# SCH_LFR_BODY_PCB_1_2025-05-22.net
KiCad netlist of a schematic drawn in EasyEDA
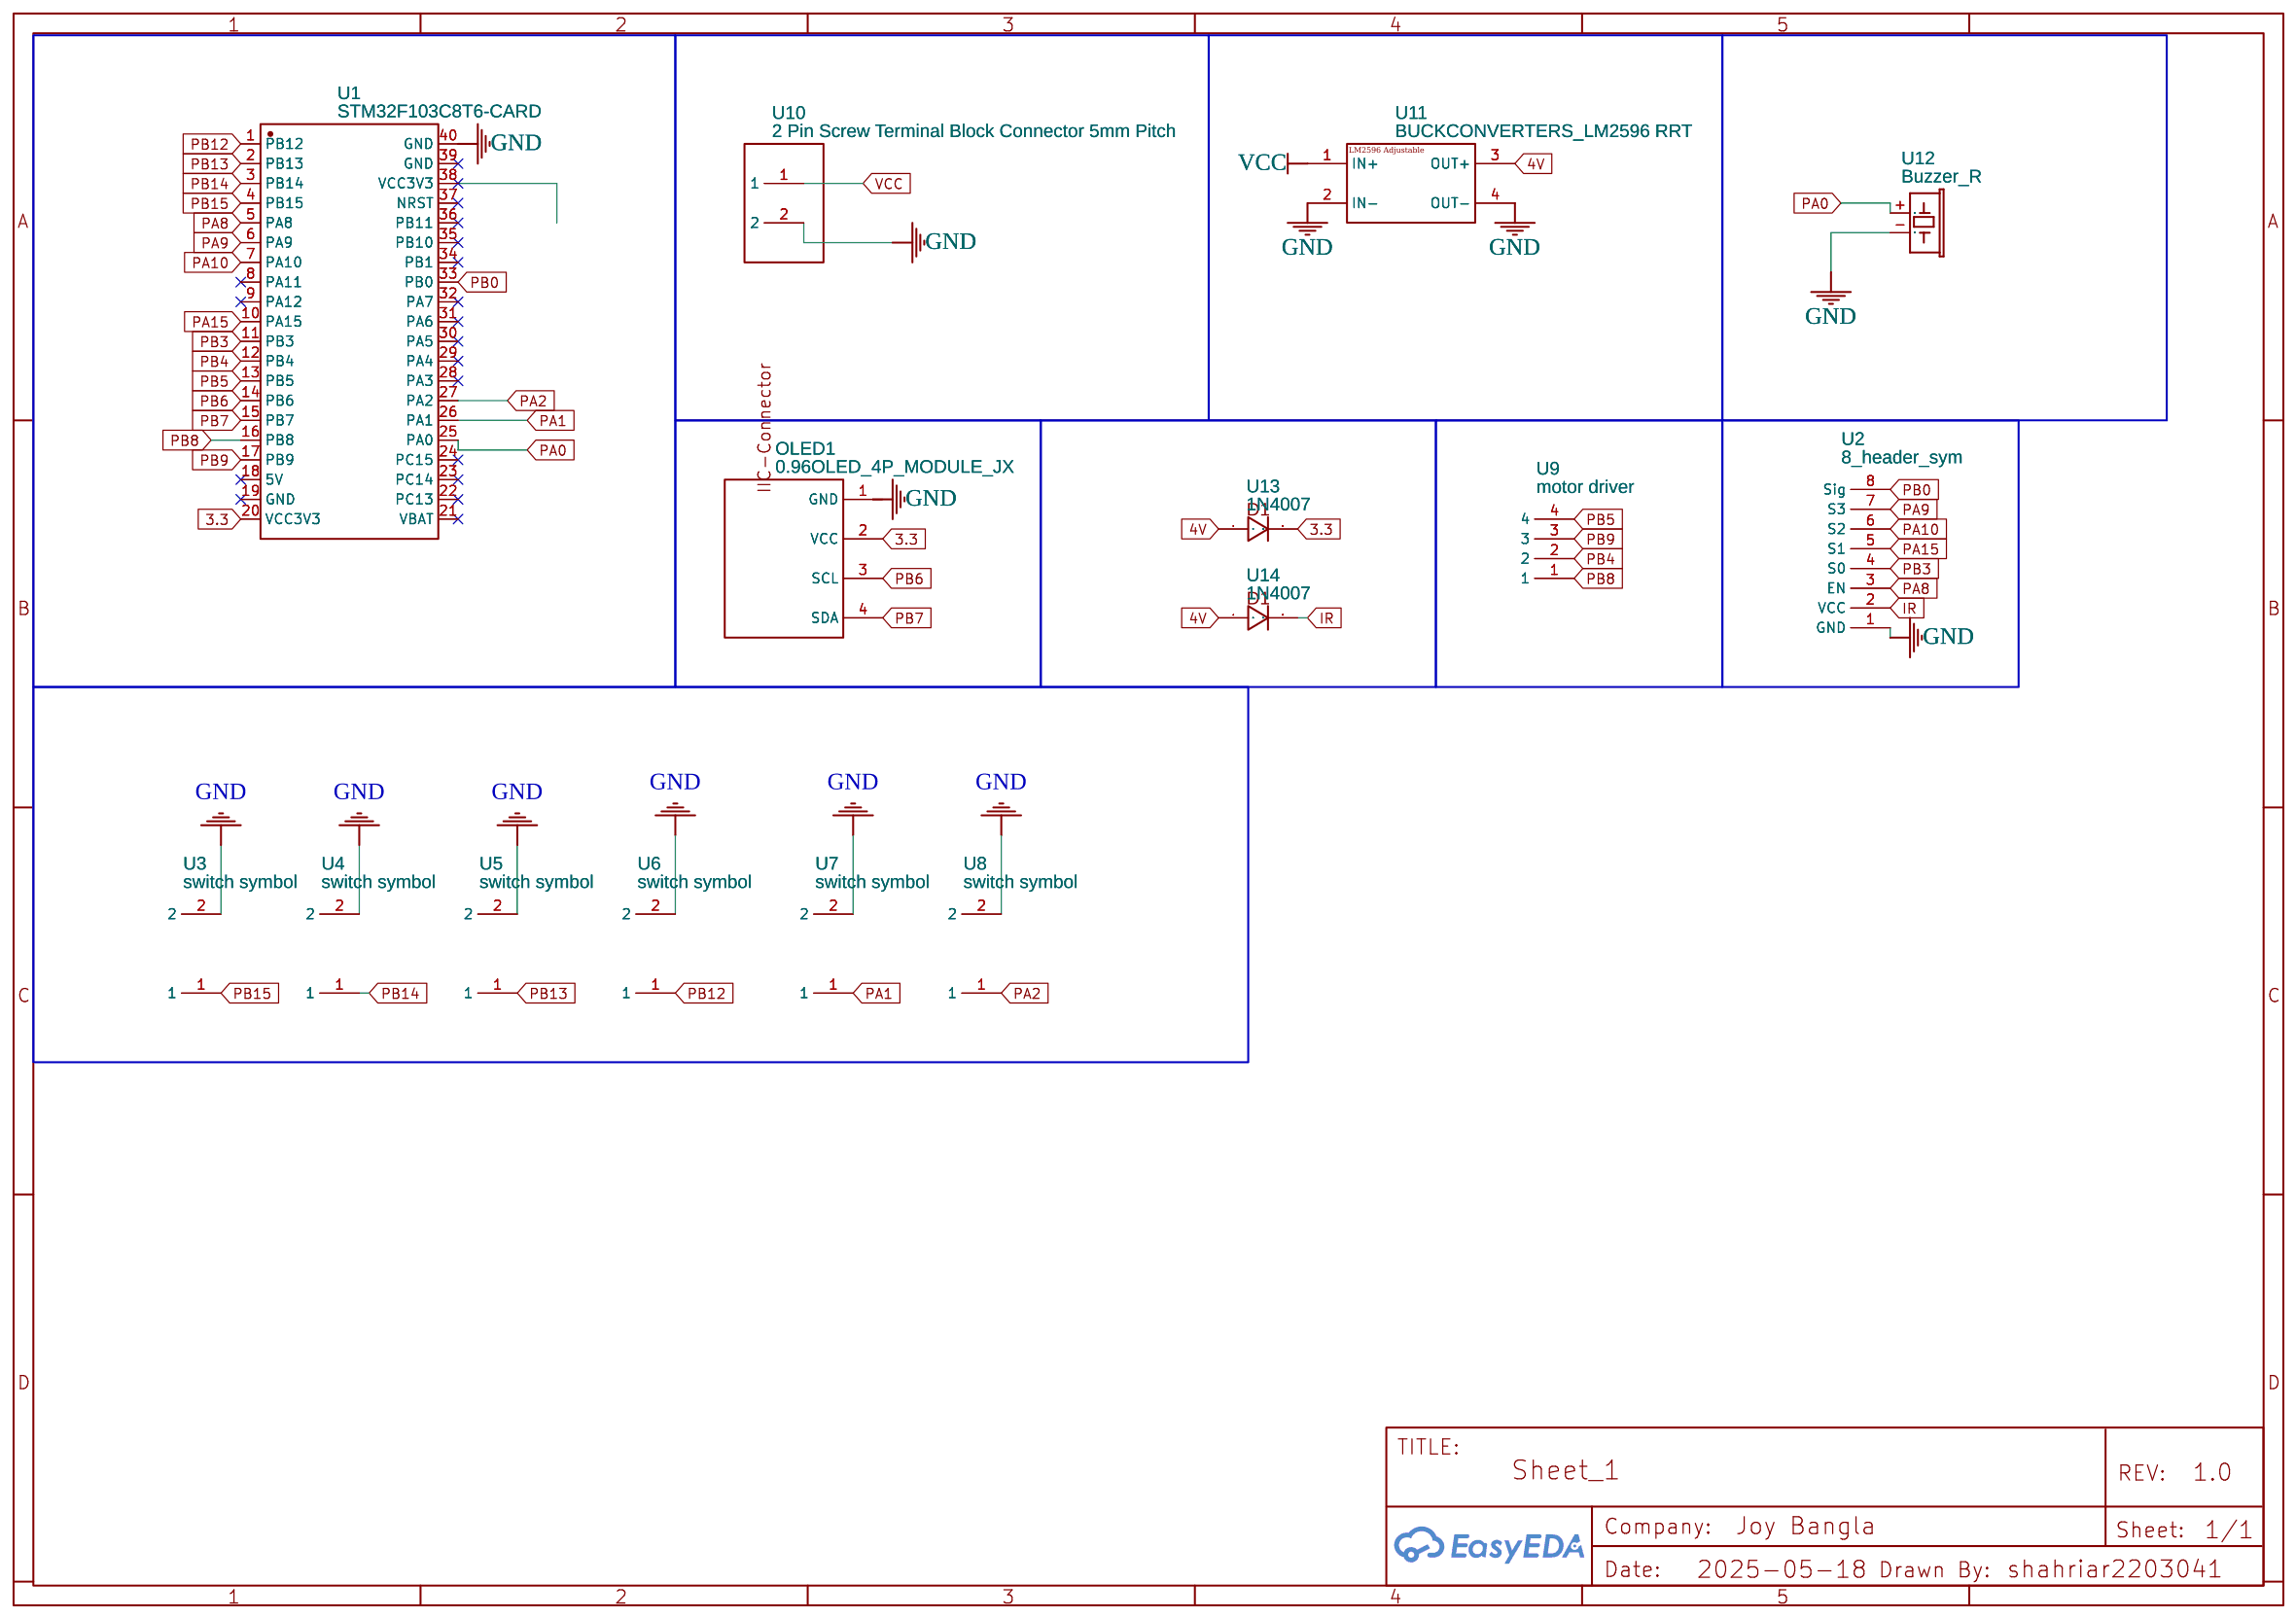
[diagram p0: schematic sheet]

(export (version "E")
  (design (tool "Eeschema 10.0.6"))
  (components
    (comp (ref "OLED1") (value "0.96OLED_4P_MODULE_JX") (libsource (lib "") (part "0.96OLED_4P_MODULE_JX")))
    (comp (ref "U1")
      (value "STM32F103C8T6-CARD")
      (fields (field (name "Manufacturer Part") "STM32F103C8T6-Card"))
      (libsource (lib "") (part "STM32F103C8T6-CARD"))
    )
    (comp (ref "U2") (value "8_header_sym") (libsource (lib "") (part "8_header_sym")))
    (comp (ref "U3") (value "switch symbol") (libsource (lib "") (part "switch symbol")))
    (comp (ref "U4") (value "switch symbol") (libsource (lib "") (part "switch symbol")))
    (comp (ref "U5") (value "switch symbol") (libsource (lib "") (part "switch symbol")))
    (comp (ref "U6") (value "switch symbol") (libsource (lib "") (part "switch symbol")))
    (comp (ref "U7") (value "switch symbol") (libsource (lib "") (part "switch symbol")))
    (comp (ref "U8") (value "switch symbol") (libsource (lib "") (part "switch symbol")))
    (comp (ref "U9") (value "motor driver") (libsource (lib "") (part "motor driver")))
    (comp (ref "U10")
      (value "2 Pin Screw Terminal Block Connector 5mm Pitch")
      (fields (field (name "Manufacturer Part") "EK8365C") (field (name "Manufacturer") "Gikfun"))
      (libsource (lib "") (part "Gikfun 2 Pin Screw Terminal Block Connector 5mm Pitch EK8365C Schematic"))
    )
    (comp (ref "U11")
      (value "BUCKCONVERTERS_LM2596 RRT")
      (libsource (lib "") (part "BuckConverters_LM2596_Adj"))
    )
    (comp (ref "U12") (value "Buzzer_R") (libsource (lib "") (part "Buzzer_R")))
    (comp (ref "U13") (value "1N4007") (libsource (lib "") (part "1N4007")))
    (comp (ref "U14") (value "1N4007") (libsource (lib "") (part "1N4007")))
  )
  (nets
    (net (code "1") (name "3.3") (class "Default")
      (node (ref "OLED1") (pin "2") (pinfunction "VCC_2") (pintype "unspecified"))
      (node (ref "U1") (pin "20") (pinfunction "VCC3V3_20") (pintype "unspecified"))
      (node (ref "U13") (pin "2") (pinfunction "1_2") (pintype "unspecified"))
    )
    (net (code "2") (name "4V") (class "Default")
      (node (ref "U11") (pin "3") (pinfunction "OUT+_3") (pintype "unspecified"))
      (node (ref "U13") (pin "1") (pinfunction "2_1") (pintype "unspecified"))
      (node (ref "U14") (pin "1") (pinfunction "2_1") (pintype "unspecified"))
    )
    (net (code "3") (name "GND") (class "Default")
      (node (ref "OLED1") (pin "1") (pinfunction "GND_1") (pintype "unspecified"))
      (node (ref "U1") (pin "40") (pinfunction "GND_40") (pintype "unspecified"))
      (node (ref "U10") (pin "2") (pinfunction "2_2") (pintype "unspecified"))
      (node (ref "U11") (pin "2") (pinfunction "IN-_2") (pintype "unspecified"))
      (node (ref "U11") (pin "4") (pinfunction "OUT-_4") (pintype "unspecified"))
      (node (ref "U12") (pin "-") (pinfunction "2_-") (pintype "unspecified"))
      (node (ref "U2") (pin "1") (pinfunction "GND_1") (pintype "unspecified"))
      (node (ref "U3") (pin "2") (pinfunction "2_2") (pintype "unspecified"))
      (node (ref "U4") (pin "2") (pinfunction "2_2") (pintype "unspecified"))
      (node (ref "U5") (pin "2") (pinfunction "2_2") (pintype "unspecified"))
      (node (ref "U6") (pin "2") (pinfunction "2_2") (pintype "unspecified"))
      (node (ref "U7") (pin "2") (pinfunction "2_2") (pintype "unspecified"))
      (node (ref "U8") (pin "2") (pinfunction "2_2") (pintype "unspecified"))
    )
    (net (code "4") (name "IR") (class "Default")
      (node (ref "U14") (pin "2") (pinfunction "1_2") (pintype "unspecified"))
      (node (ref "U2") (pin "2") (pinfunction "VCC_2") (pintype "unspecified"))
    )
    (net (code "5") (name "PA0") (class "Default")
      (node (ref "U1") (pin "25") (pinfunction "PA0_25") (pintype "unspecified"))
      (node (ref "U12") (pin "+") (pinfunction "1_+") (pintype "unspecified"))
    )
    (net (code "6") (name "PA1") (class "Default")
      (node (ref "U1") (pin "26") (pinfunction "PA1_26") (pintype "unspecified"))
      (node (ref "U7") (pin "1") (pinfunction "1_1") (pintype "unspecified"))
    )
    (net (code "7") (name "PA2") (class "Default")
      (node (ref "U1") (pin "27") (pinfunction "PA2_27") (pintype "unspecified"))
      (node (ref "U8") (pin "1") (pinfunction "1_1") (pintype "unspecified"))
    )
    (net (code "8") (name "PA8") (class "Default")
      (node (ref "U1") (pin "5") (pinfunction "PA8_5") (pintype "unspecified"))
      (node (ref "U2") (pin "3") (pinfunction "EN_3") (pintype "unspecified"))
    )
    (net (code "9") (name "PA9") (class "Default")
      (node (ref "U1") (pin "6") (pinfunction "PA9_6") (pintype "unspecified"))
      (node (ref "U2") (pin "7") (pinfunction "S3_7") (pintype "unspecified"))
    )
    (net (code "10") (name "PA10") (class "Default")
      (node (ref "U1") (pin "7") (pinfunction "PA10_7") (pintype "unspecified"))
      (node (ref "U2") (pin "6") (pinfunction "S2_6") (pintype "unspecified"))
    )
    (net (code "11") (name "PA15") (class "Default")
      (node (ref "U1") (pin "10") (pinfunction "PA15_10") (pintype "unspecified"))
      (node (ref "U2") (pin "5") (pinfunction "S1_5") (pintype "unspecified"))
    )
    (net (code "12") (name "PB0") (class "Default")
      (node (ref "U1") (pin "33") (pinfunction "PB0_33") (pintype "unspecified"))
      (node (ref "U2") (pin "8") (pinfunction "Sig_8") (pintype "unspecified"))
    )
    (net (code "13") (name "PB3") (class "Default")
      (node (ref "U1") (pin "11") (pinfunction "PB3_11") (pintype "unspecified"))
      (node (ref "U2") (pin "4") (pinfunction "S0_4") (pintype "unspecified"))
    )
    (net (code "14") (name "PB4") (class "Default")
      (node (ref "U1") (pin "12") (pinfunction "PB4_12") (pintype "unspecified"))
      (node (ref "U9") (pin "2") (pinfunction "2_2") (pintype "unspecified"))
    )
    (net (code "15") (name "PB5") (class "Default")
      (node (ref "U1") (pin "13") (pinfunction "PB5_13") (pintype "unspecified"))
      (node (ref "U9") (pin "4") (pinfunction "4_4") (pintype "unspecified"))
    )
    (net (code "16") (name "PB6") (class "Default")
      (node (ref "OLED1") (pin "3") (pinfunction "SCL_3") (pintype "unspecified"))
      (node (ref "U1") (pin "14") (pinfunction "PB6_14") (pintype "unspecified"))
    )
    (net (code "17") (name "PB7") (class "Default")
      (node (ref "OLED1") (pin "4") (pinfunction "SDA_4") (pintype "unspecified"))
      (node (ref "U1") (pin "15") (pinfunction "PB7_15") (pintype "unspecified"))
    )
    (net (code "18") (name "PB8") (class "Default")
      (node (ref "U1") (pin "16") (pinfunction "PB8_16") (pintype "unspecified"))
      (node (ref "U9") (pin "1") (pinfunction "1_1") (pintype "unspecified"))
    )
    (net (code "19") (name "PB9") (class "Default")
      (node (ref "U1") (pin "17") (pinfunction "PB9_17") (pintype "unspecified"))
      (node (ref "U9") (pin "3") (pinfunction "3_3") (pintype "unspecified"))
    )
    (net (code "20") (name "PB12") (class "Default")
      (node (ref "U1") (pin "1") (pinfunction "PB12_1") (pintype "unspecified"))
      (node (ref "U6") (pin "1") (pinfunction "1_1") (pintype "unspecified"))
    )
    (net (code "21") (name "PB13") (class "Default")
      (node (ref "U1") (pin "2") (pinfunction "PB13_2") (pintype "unspecified"))
      (node (ref "U5") (pin "1") (pinfunction "1_1") (pintype "unspecified"))
    )
    (net (code "22") (name "PB14") (class "Default")
      (node (ref "U1") (pin "3") (pinfunction "PB14_3") (pintype "unspecified"))
      (node (ref "U4") (pin "1") (pinfunction "1_1") (pintype "unspecified"))
    )
    (net (code "23") (name "PB15") (class "Default")
      (node (ref "U1") (pin "4") (pinfunction "PB15_4") (pintype "unspecified"))
      (node (ref "U3") (pin "1") (pinfunction "1_1") (pintype "unspecified"))
    )
    (net (code "24") (name "VCC") (class "Default")
      (node (ref "U10") (pin "1") (pinfunction "1_1") (pintype "unspecified"))
      (node (ref "U11") (pin "1") (pinfunction "IN+_1") (pintype "unspecified"))
    )
    (net (code "25") (name "unconnected-(U1-5V-Pad18)") (class "Default")
      (node (ref "U1") (pin "18") (pinfunction "5V_18") (pintype "unspecified+no_connect"))
    )
    (net (code "26") (name "unconnected-(U1-GND-Pad19)") (class "Default")
      (node (ref "U1") (pin "19") (pinfunction "GND_19") (pintype "unspecified+no_connect"))
    )
    (net (code "27") (name "unconnected-(U1-GND-Pad39)") (class "Default")
      (node (ref "U1") (pin "39") (pinfunction "GND_39") (pintype "unspecified+no_connect"))
    )
    (net (code "28") (name "unconnected-(U1-NRST-Pad37)") (class "Default")
      (node (ref "U1") (pin "37") (pinfunction "NRST_37") (pintype "unspecified+no_connect"))
    )
    (net (code "29") (name "unconnected-(U1-PA3-Pad28)") (class "Default")
      (node (ref "U1") (pin "28") (pinfunction "PA3_28") (pintype "unspecified+no_connect"))
    )
    (net (code "30") (name "unconnected-(U1-PA4-Pad29)") (class "Default")
      (node (ref "U1") (pin "29") (pinfunction "PA4_29") (pintype "unspecified+no_connect"))
    )
    (net (code "31") (name "unconnected-(U1-PA5-Pad30)") (class "Default")
      (node (ref "U1") (pin "30") (pinfunction "PA5_30") (pintype "unspecified+no_connect"))
    )
    (net (code "32") (name "unconnected-(U1-PA6-Pad31)") (class "Default")
      (node (ref "U1") (pin "31") (pinfunction "PA6_31") (pintype "unspecified+no_connect"))
    )
    (net (code "33") (name "unconnected-(U1-PA7-Pad32)") (class "Default")
      (node (ref "U1") (pin "32") (pinfunction "PA7_32") (pintype "unspecified+no_connect"))
    )
    (net (code "34") (name "unconnected-(U1-PA11-Pad8)") (class "Default")
      (node (ref "U1") (pin "8") (pinfunction "PA11_8") (pintype "unspecified+no_connect"))
    )
    (net (code "35") (name "unconnected-(U1-PA12-Pad9)") (class "Default")
      (node (ref "U1") (pin "9") (pinfunction "PA12_9") (pintype "unspecified+no_connect"))
    )
    (net (code "36") (name "unconnected-(U1-PB1-Pad34)") (class "Default")
      (node (ref "U1") (pin "34") (pinfunction "PB1_34") (pintype "unspecified+no_connect"))
    )
    (net (code "37") (name "unconnected-(U1-PB10-Pad35)") (class "Default")
      (node (ref "U1") (pin "35") (pinfunction "PB10_35") (pintype "unspecified+no_connect"))
    )
    (net (code "38") (name "unconnected-(U1-PB11-Pad36)") (class "Default")
      (node (ref "U1") (pin "36") (pinfunction "PB11_36") (pintype "unspecified+no_connect"))
    )
    (net (code "39") (name "unconnected-(U1-PC13-Pad22)") (class "Default")
      (node (ref "U1") (pin "22") (pinfunction "PC13_22") (pintype "unspecified+no_connect"))
    )
    (net (code "40") (name "unconnected-(U1-PC14-Pad23)") (class "Default")
      (node (ref "U1") (pin "23") (pinfunction "PC14_23") (pintype "unspecified+no_connect"))
    )
    (net (code "41") (name "unconnected-(U1-PC15-Pad24)") (class "Default")
      (node (ref "U1") (pin "24") (pinfunction "PC15_24") (pintype "unspecified+no_connect"))
    )
    (net (code "42") (name "unconnected-(U1-VBAT-Pad21)") (class "Default")
      (node (ref "U1") (pin "21") (pinfunction "VBAT_21") (pintype "unspecified+no_connect"))
    )
    (net (code "43") (name "unconnected-(U1-VCC3V3-Pad38)") (class "Default")
      (node (ref "U1") (pin "38") (pinfunction "VCC3V3_38") (pintype "unspecified+no_connect"))
    )
  )
)
